# IoTSchem.net
KiCad netlist of a schematic drawn in EAGLE
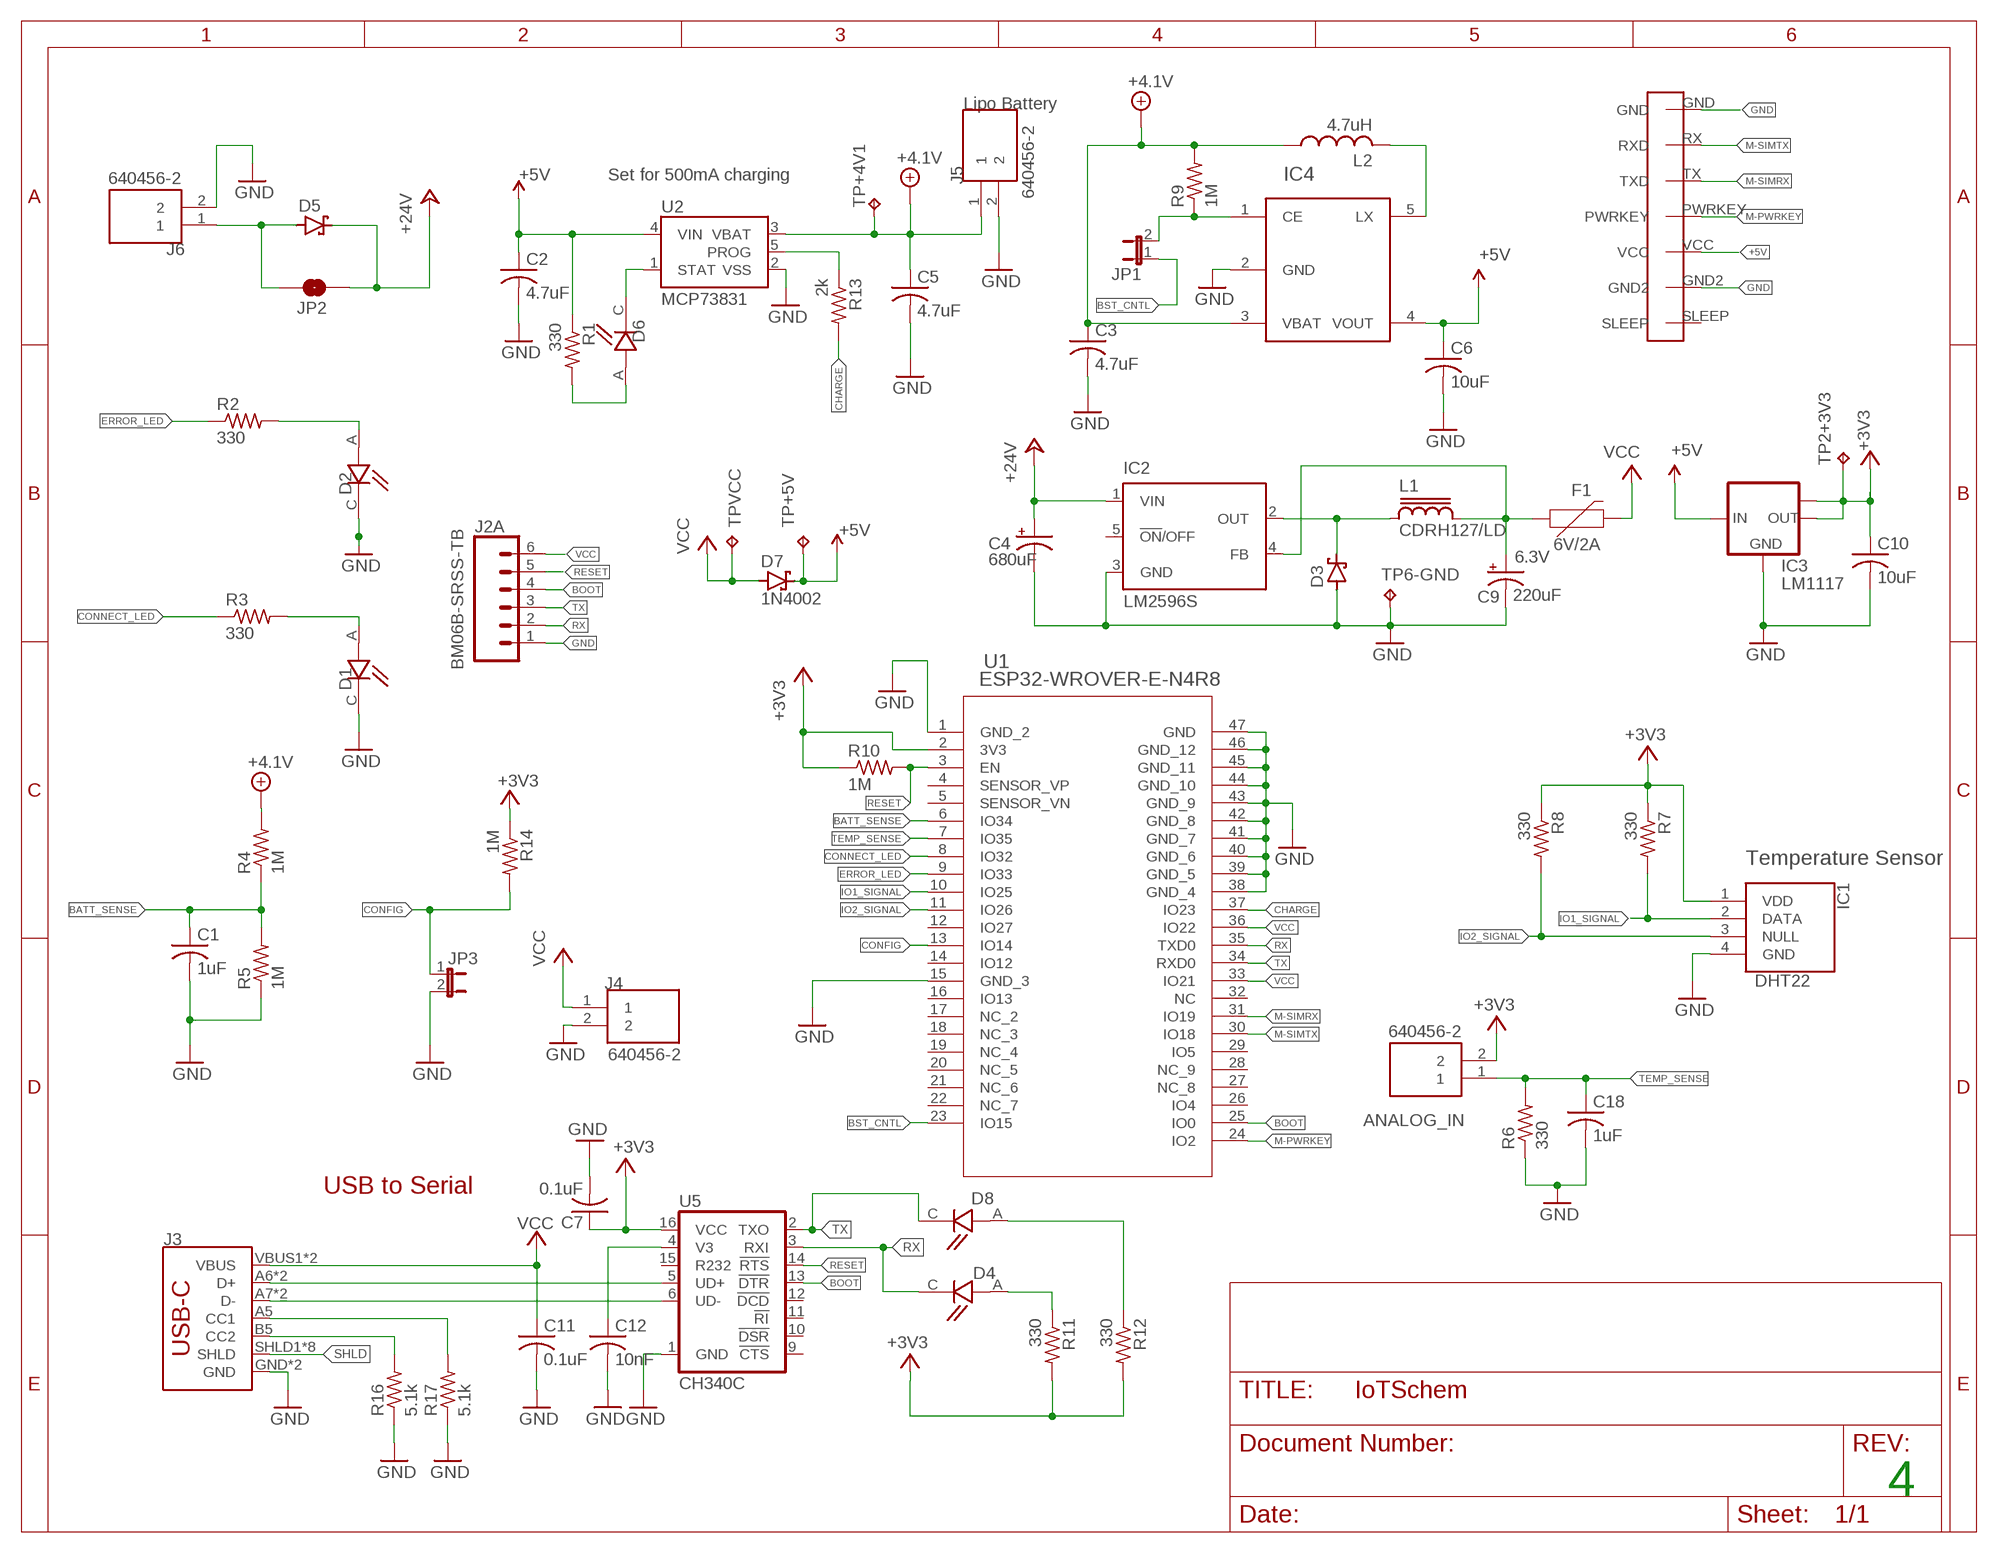
[diagram p0: schematic, sheet 1]

(export (version "E")
  (design (tool "Eeschema 10.0.6"))
  (components
    (comp (ref "ANALOG_IN")
      (value "640456-2")
      (footprint "eagle-import:TE_640456-2")
      (fields (field (name "DIGI-KEY_PART_NUMBER") "A1921-ND") (field (name "MF") "TE Connectivity"))
      (libsource (lib "eagle-import") (part "640456-2"))
    )
    (comp (ref "C1")
      (value "1uF")
      (footprint "eagle-import:C0805")
      (fields (field (name "DIGIKEYPART#") "311-1365-1-ND"))
      (libsource (lib "eagle-import") (part "C-USC0805"))
    )
    (comp (ref "C2")
      (value "4.7uF")
      (footprint "eagle-import:C0805")
      (fields (field (name "DIGIKEYPART#") "1276-6722-1-ND"))
      (libsource (lib "eagle-import") (part "C-USC0805"))
    )
    (comp (ref "C3")
      (value "4.7uF")
      (footprint "eagle-import:C0805")
      (fields (field (name "DIGIKEYPART#") "1276-6722-1-ND"))
      (libsource (lib "eagle-import") (part "C-USC0805"))
    )
    (comp (ref "C4")
      (value "680uF")
      (footprint "eagle-import:E5-10,5")
      (fields (field (name "VOLTAGE") "25V"))
      (libsource (lib "eagle-import") (part "CPOL-USE5-10.5"))
    )
    (comp (ref "C5")
      (value "4.7uF")
      (footprint "eagle-import:C0805")
      (fields (field (name "DIGIKEYPART#") "1276-6722-1-ND"))
      (libsource (lib "eagle-import") (part "C-USC0805"))
    )
    (comp (ref "C6")
      (value "10uF")
      (footprint "eagle-import:C0805")
      (libsource (lib "eagle-import") (part "C-USC0805"))
    )
    (comp (ref "C7")
      (value "0.1uF")
      (footprint "eagle-import:C0805")
      (fields (field (name "DIGIKEYPART#") "311-1140-1-ND"))
      (libsource (lib "eagle-import") (part "C-USC0805"))
    )
    (comp (ref "C9")
      (value "220uF")
      (footprint "eagle-import:UD-6,3X5,8_NICHICON")
      (fields (field (name "VOLTAGE") "6.3V"))
      (libsource (lib "eagle-import") (part "CPOL-USUD-6,3X5,8"))
    )
    (comp (ref "C10")
      (value "10uF")
      (footprint "eagle-import:C0805")
      (fields (field (name "DIGIKEYPART#") "399-C0805C106K8PAC7800CT-ND"))
      (libsource (lib "eagle-import") (part "C-USC0805"))
    )
    (comp (ref "C11")
      (value "0.1uF")
      (footprint "eagle-import:C0805")
      (fields (field (name "DIGIKEYPART#") "311-1140-1-ND"))
      (libsource (lib "eagle-import") (part "C-USC0805"))
    )
    (comp (ref "C12")
      (value "10nF")
      (footprint "eagle-import:C0805")
      (fields (field (name "DIGIKEYPART#") "1276-1015-1-ND"))
      (libsource (lib "eagle-import") (part "C-USC0805"))
    )
    (comp (ref "C18")
      (value "1uF")
      (footprint "eagle-import:C0805")
      (fields (field (name "DIGIKEYPART#") "311-1365-1-ND"))
      (libsource (lib "eagle-import") (part "C-USC0805"))
    )
    (comp (ref "D1")
      (value "5988170107F")
      (footprint "eagle-import:LEDC2012X70N")
      (fields (field (name "DIGI-KEY_PART_NUMBER") "350-2044-1-ND") (field (name "MF") "Dialight"))
      (libsource (lib "eagle-import") (part "5988170107F"))
    )
    (comp (ref "D2")
      (value "5988170107F")
      (footprint "eagle-import:LEDC2012X70N")
      (fields (field (name "DIGI-KEY_PART_NUMBER") "350-2044-1-ND") (field (name "MF") "Dialight"))
      (libsource (lib "eagle-import") (part "5988170107F"))
    )
    (comp (ref "D3")
      (value "SCHOTTKY-DIODESMD")
      (footprint "eagle-import:SMB")
      (libsource (lib "eagle-import") (part "SCHOTTKY-DIODESMD"))
    )
    (comp (ref "D4")
      (value "5988170107F")
      (footprint "eagle-import:LEDC2012X70N")
      (fields (field (name "DIGI-KEY_PART_NUMBER") "350-2044-1-ND") (field (name "MF") "Dialight"))
      (libsource (lib "eagle-import") (part "5988170107F"))
    )
    (comp (ref "D5")
      (value "1N4002")
      (footprint "eagle-import:SMB")
      (libsource (lib "eagle-import") (part "SCHOTTKY-DIODESMD"))
    )
    (comp (ref "D6")
      (value "5988170107F")
      (footprint "eagle-import:LEDC2012X70N")
      (fields (field (name "DIGI-KEY_PART_NUMBER") "350-2044-1-ND") (field (name "MF") "Dialight"))
      (libsource (lib "eagle-import") (part "5988170107F"))
    )
    (comp (ref "D7")
      (value "1N4002")
      (footprint "eagle-import:SMB")
      (libsource (lib "eagle-import") (part "SCHOTTKY-DIODESMD"))
    )
    (comp (ref "D8")
      (value "5988170107F")
      (footprint "eagle-import:LEDC2012X70N")
      (fields (field (name "DIGI-KEY_PART_NUMBER") "350-2044-1-ND") (field (name "MF") "Dialight"))
      (libsource (lib "eagle-import") (part "5988170107F"))
    )
    (comp (ref "F1")
      (value "6V/2A")
      (footprint "eagle-import:1210")
      (libsource (lib "eagle-import") (part "PPTC_6V2A"))
    )
    (comp (ref "IC1")
      (value "DHT22")
      (footprint "eagle-import:DHT22")
      (fields (field (name "DIGIKEYPART#") "1528-1504-ND"))
      (libsource (lib "eagle-import") (part "DHT22"))
    )
    (comp (ref "IC2")
      (value "LM2596S")
      (footprint "eagle-import:TO263-5")
      (fields
        (field (name "MF") "NATIONAL SEMICONDUCTOR")
        (field (name "MPN") "LM2596S-ADJ/NOPB")
        (field (name "DIGIKEYPART#") "2156-LM2596SX-5.0/NOPB-ND")
      )
      (libsource (lib "eagle-import") (part "LM2596S"))
    )
    (comp (ref "IC3")
      (value "LM1117MPX-3.3")
      (footprint "eagle-import:SOT223")
      (fields (field (name "DIGIKEYPART#") "LM1117IMP-3.3/NOPBCT-ND"))
      (libsource (lib "eagle-import") (part "LM1117MPX-3.3"))
    )
    (comp (ref "IC4")
      (value "XC9140")
      (footprint "eagle-import:SOT-25")
      (fields (field (name "DIGIKEYPART#") "893-1181-1-ND"))
      (libsource (lib "eagle-import") (part "XC9140"))
    )
    (comp (ref "J1")
      (value "SIM7000A")
      (footprint "eagle-import:SIM7000A")
      (libsource (lib "eagle-import") (part "SIM7000A"))
    )
    (comp (ref "J2")
      (value "BM06B-SRSS-TB")
      (footprint "eagle-import:JST-6-SMD-HORI-1.0MM")
      (libsource (lib "eagle-import") (part "JST_6_PIN_HORIZONTAL"))
    )
    (comp (ref "J3")
      (value "USB_C16PIN")
      (footprint "eagle-import:USB-C-16P")
      (libsource (lib "eagle-import") (part "USB_C16PIN"))
    )
    (comp (ref "J4")
      (value "640456-2")
      (footprint "eagle-import:TE_640456-2")
      (fields (field (name "DIGI-KEY_PART_NUMBER") "A1921-ND") (field (name "MF") "TE Connectivity"))
      (libsource (lib "eagle-import") (part "640456-2"))
    )
    (comp (ref "J5")
      (value "640456-2")
      (footprint "eagle-import:TE_640456-2")
      (fields (field (name "DIGI-KEY_PART_NUMBER") "A1921-ND") (field (name "MF") "TE Connectivity"))
      (libsource (lib "eagle-import") (part "640456-2"))
    )
    (comp (ref "J6")
      (value "640456-2")
      (footprint "eagle-import:TE_640456-2")
      (fields (field (name "DIGI-KEY_PART_NUMBER") "A1921-ND") (field (name "MF") "TE Connectivity"))
      (libsource (lib "eagle-import") (part "640456-2"))
    )
    (comp (ref "JP1")
      (value "JP1E")
      (footprint "eagle-import:JP1")
      (libsource (lib "eagle-import") (part "JP1E"))
    )
    (comp (ref "JP2")
      (value "JUMPER-SMT_2_NO_SILK")
      (footprint "eagle-import:SMT-JUMPER_2_NO_SILK")
      (libsource (lib "eagle-import") (part "JUMPER-SMT_2_NO_SILK"))
    )
    (comp (ref "JP3")
      (value "JP1E")
      (footprint "eagle-import:JP1")
      (libsource (lib "eagle-import") (part "JP1E"))
    )
    (comp (ref "L1")
      (value "CDRH127/LD")
      (footprint "eagle-import:CDRH127_LD")
      (libsource (lib "eagle-import") (part "CDRH127/LD"))
    )
    (comp (ref "L2")
      (value "4.7uH")
      (footprint "eagle-import:L2825P")
      (libsource (lib "eagle-import") (part "L-USL2825P"))
    )
    (comp (ref "R1")
      (value "330")
      (footprint "eagle-import:R0805")
      (libsource (lib "eagle-import") (part "R-US_R0805"))
    )
    (comp (ref "R2")
      (value "330")
      (footprint "eagle-import:R0805")
      (fields (field (name "DIGIKEYPART#") "RMCF0805JT330RCT-ND"))
      (libsource (lib "eagle-import") (part "R-US_R0805"))
    )
    (comp (ref "R3")
      (value "330")
      (footprint "eagle-import:R0805")
      (fields (field (name "DIGIKEYPART#") "RMCF0805JT330RCT-ND"))
      (libsource (lib "eagle-import") (part "R-US_R0805"))
    )
    (comp (ref "R4")
      (value "1M")
      (footprint "eagle-import:R0805")
      (fields (field (name "DIGIKEYPART#") "RMCF0805JT1M00CT-ND"))
      (libsource (lib "eagle-import") (part "R-US_R0805"))
    )
    (comp (ref "R5")
      (value "1M")
      (footprint "eagle-import:R0805")
      (fields (field (name "DIGIKEYPART#") "RMCF0805JT1M00CT-ND"))
      (libsource (lib "eagle-import") (part "R-US_R0805"))
    )
    (comp (ref "R6")
      (value "330")
      (footprint "eagle-import:R0805")
      (fields (field (name "DIGIKEYPART#") "RMCF0805JT330RCT-ND"))
      (libsource (lib "eagle-import") (part "R-US_R0805"))
    )
    (comp (ref "R7")
      (value "330")
      (footprint "eagle-import:R0805")
      (fields (field (name "DIGIKEYPART#") "RMCF0805JT330RCT-ND"))
      (libsource (lib "eagle-import") (part "R-US_R0805"))
    )
    (comp (ref "R8")
      (value "330")
      (footprint "eagle-import:R0805")
      (fields (field (name "DIGIKEYPART#") "RMCF0805JT330RCT-ND"))
      (libsource (lib "eagle-import") (part "R-US_R0805"))
    )
    (comp (ref "R9")
      (value "1M")
      (footprint "eagle-import:R0805")
      (fields (field (name "DIGIKEYPART#") "RMCF0805JT1M00CT-ND"))
      (libsource (lib "eagle-import") (part "R-US_R0805"))
    )
    (comp (ref "R10")
      (value "1M")
      (footprint "eagle-import:R0805")
      (fields (field (name "DIGIKEYPART#") "RMCF0805JT1M00CT-ND"))
      (libsource (lib "eagle-import") (part "R-US_R0805"))
    )
    (comp (ref "R11")
      (value "330")
      (footprint "eagle-import:R0805")
      (fields (field (name "DIGIKEYPART#") "RMCF0805JT330RCT-ND"))
      (libsource (lib "eagle-import") (part "R-US_R0805"))
    )
    (comp (ref "R12")
      (value "330")
      (footprint "eagle-import:R0805")
      (fields (field (name "DIGIKEYPART#") "RMCF0805JT330RCT-ND"))
      (libsource (lib "eagle-import") (part "R-US_R0805"))
    )
    (comp (ref "R13")
      (value "2k")
      (footprint "eagle-import:R0805")
      (fields (field (name "DIGIKEYPART#") "RMCF0805FT2K00CT-ND"))
      (libsource (lib "eagle-import") (part "R-US_R0805"))
    )
    (comp (ref "R14")
      (value "1M")
      (footprint "eagle-import:R0805")
      (fields (field (name "DIGIKEYPART#") "RMCF0805JT1M00CT-ND"))
      (libsource (lib "eagle-import") (part "R-US_R0805"))
    )
    (comp (ref "R16")
      (value "5.1k")
      (footprint "eagle-import:R0805")
      (fields (field (name "DIGIKEYPART#") "RMCF0805JT5K10CT-ND"))
      (libsource (lib "eagle-import") (part "R-US_R0805"))
    )
    (comp (ref "R17")
      (value "5.1k")
      (footprint "eagle-import:R0805")
      (fields (field (name "DIGIKEYPART#") "RMCF0805JT5K10CT-ND"))
      (libsource (lib "eagle-import") (part "R-US_R0805"))
    )
    (comp (ref "TP+4V1")
      (value "TPB1,27")
      (footprint "eagle-import:B1,27")
      (libsource (lib "eagle-import") (part "TPB1,27"))
    )
    (comp (ref "TP+5V")
      (value "TPB1,27")
      (footprint "eagle-import:B1,27")
      (libsource (lib "eagle-import") (part "TPB1,27"))
    )
    (comp (ref "TP2+3V3")
      (value "TPB1,27")
      (footprint "eagle-import:B1,27")
      (libsource (lib "eagle-import") (part "TPB1,27"))
    )
    (comp (ref "TP6-GND")
      (value "TPB1,27")
      (footprint "eagle-import:B1,27")
      (libsource (lib "eagle-import") (part "TPB1,27"))
    )
    (comp (ref "TPVCC")
      (value "TPB1,27")
      (footprint "eagle-import:B1,27")
      (libsource (lib "eagle-import") (part "TPB1,27"))
    )
    (comp (ref "U1")
      (value "ESP32-WROVER-E-N4R8")
      (footprint "eagle-import:ESP32­WROVER­E_ESP32­WROVER­IE")
      (fields (field (name "COPYRIGHT") "Copyright (C) 2022 Ultra Librarian. All rights reserved."))
      (libsource (lib "eagle-import") (part "ESP32-WROVER-E-N4R8"))
    )
    (comp (ref "U2")
      (value "MCP73831")
      (footprint "eagle-import:SOT23-5")
      (fields (field (name "DIGIKEYPART#") "MCP73831T-2DCI/OTCT-ND"))
      (libsource (lib "eagle-import") (part "MCP73831"))
    )
    (comp (ref "U5")
      (value "CH340C")
      (footprint "eagle-import:SO016")
      (libsource (lib "eagle-import") (part "CH340C"))
    )
  )
  (nets
    (net (code "1") (name "+3V3") (class "Default")
      (node (ref "ANALOG_IN") (pin "2") (pinfunction "2_2") (pintype "passive"))
      (node (ref "C10") (pin "1") (pinfunction "1_1") (pintype "passive"))
      (node (ref "C7") (pin "1") (pinfunction "1_1") (pintype "passive"))
      (node (ref "IC1") (pin "1") (pinfunction "VDD_1") (pintype "bidirectional"))
      (node (ref "IC3") (pin "2") (pinfunction "OUT_2") (pintype "passive"))
      (node (ref "IC3") (pin "TAB") (pinfunction "OUT1_TAB") (pintype "passive"))
      (node (ref "R10") (pin "1") (pinfunction "1_1") (pintype "passive"))
      (node (ref "R11") (pin "2") (pinfunction "2_2") (pintype "passive"))
      (node (ref "R12") (pin "2") (pinfunction "2_2") (pintype "passive"))
      (node (ref "R14") (pin "1") (pinfunction "1_1") (pintype "passive"))
      (node (ref "R7") (pin "1") (pinfunction "1_1") (pintype "passive"))
      (node (ref "R8") (pin "1") (pinfunction "1_1") (pintype "passive"))
      (node (ref "TP2+3V3") (pin "TP") (pinfunction "TP_TP") (pintype "input"))
      (node (ref "U1") (pin "2") (pinfunction "3V3_2") (pintype "power_in"))
      (node (ref "U5") (pin "16") (pinfunction "VCC_16") (pintype "bidirectional"))
    )
    (net (code "2") (name "+4.1V") (class "Default")
      (node (ref "C3") (pin "1") (pinfunction "1_1") (pintype "passive"))
      (node (ref "C5") (pin "1") (pinfunction "1_1") (pintype "passive"))
      (node (ref "IC4") (pin "3") (pinfunction "VBAT_3") (pintype "bidirectional"))
      (node (ref "J5") (pin "1") (pinfunction "1_1") (pintype "passive"))
      (node (ref "L2") (pin "1") (pinfunction "1_1") (pintype "passive"))
      (node (ref "R4") (pin "2") (pinfunction "2_2") (pintype "passive"))
      (node (ref "R9") (pin "2") (pinfunction "2_2") (pintype "passive"))
      (node (ref "TP+4V1") (pin "TP") (pinfunction "TP_TP") (pintype "input"))
      (node (ref "U2") (pin "3") (pinfunction "VBAT_3") (pintype "power_in"))
    )
    (net (code "3") (name "+5V") (class "Default")
      (node (ref "C2") (pin "1") (pinfunction "1_1") (pintype "passive"))
      (node (ref "C6") (pin "1") (pinfunction "1_1") (pintype "passive"))
      (node (ref "D7") (pin "C") (pinfunction "C_C") (pintype "passive"))
      (node (ref "IC3") (pin "3") (pinfunction "IN_3") (pintype "input"))
      (node (ref "IC4") (pin "4") (pinfunction "VOUT_4") (pintype "bidirectional"))
      (node (ref "J1") (pin "VCC") (pinfunction "VCC_VCC") (pintype "bidirectional"))
      (node (ref "R1") (pin "1") (pinfunction "1_1") (pintype "passive"))
      (node (ref "TP+5V") (pin "TP") (pinfunction "TP_TP") (pintype "input"))
      (node (ref "U2") (pin "4") (pinfunction "VIN_4") (pintype "power_in"))
    )
    (net (code "4") (name "+24V") (class "Default")
      (node (ref "C4") (pin "+") (pinfunction "+_+") (pintype "passive"))
      (node (ref "D5") (pin "C") (pinfunction "C_C") (pintype "passive"))
      (node (ref "IC2") (pin "1") (pinfunction "VIN_1") (pintype "input"))
      (node (ref "JP2") (pin "2") (pinfunction "2_2") (pintype "passive"))
    )
    (net (code "5") (name "BATT_SENSE") (class "Default")
      (node (ref "C1") (pin "1") (pinfunction "1_1") (pintype "passive"))
      (node (ref "R4") (pin "1") (pinfunction "1_1") (pintype "passive"))
      (node (ref "R5") (pin "2") (pinfunction "2_2") (pintype "passive"))
      (node (ref "U1") (pin "6") (pinfunction "IO34_6") (pintype "input"))
    )
    (net (code "6") (name "BOOT") (class "Default")
      (node (ref "J2") (pin "4") (pinfunction "4_4") (pintype "passive"))
      (node (ref "U1") (pin "25") (pinfunction "IO0_25") (pintype "bidirectional"))
      (node (ref "U5") (pin "13") (pinfunction "~{DTR}_13") (pintype "bidirectional"))
    )
    (net (code "7") (name "BST_CNTL") (class "Default")
      (node (ref "JP1") (pin "1") (pinfunction "1_1") (pintype "passive"))
      (node (ref "U1") (pin "23") (pinfunction "IO15_23") (pintype "bidirectional"))
    )
    (net (code "8") (name "CHARGE") (class "Default")
      (node (ref "R13") (pin "1") (pinfunction "1_1") (pintype "passive"))
      (node (ref "U1") (pin "37") (pinfunction "IO23_37") (pintype "bidirectional"))
      (node (ref "U2") (pin "5") (pinfunction "PROG_5") (pintype "input"))
    )
    (net (code "9") (name "CONFIG") (class "Default")
      (node (ref "JP3") (pin "1") (pinfunction "1_1") (pintype "passive"))
      (node (ref "R14") (pin "2") (pinfunction "2_2") (pintype "passive"))
      (node (ref "U1") (pin "13") (pinfunction "IO14_13") (pintype "bidirectional"))
    )
    (net (code "10") (name "CONNECT_LED") (class "Default")
      (node (ref "R3") (pin "1") (pinfunction "1_1") (pintype "passive"))
      (node (ref "U1") (pin "8") (pinfunction "IO32_8") (pintype "bidirectional"))
    )
    (net (code "11") (name "ERROR_LED") (class "Default")
      (node (ref "R2") (pin "1") (pinfunction "1_1") (pintype "passive"))
      (node (ref "U1") (pin "9") (pinfunction "IO33_9") (pintype "bidirectional"))
    )
    (net (code "12") (name "GND") (class "Default")
      (node (ref "C1") (pin "2") (pinfunction "2_2") (pintype "passive"))
      (node (ref "C10") (pin "2") (pinfunction "2_2") (pintype "passive"))
      (node (ref "C11") (pin "2") (pinfunction "2_2") (pintype "passive"))
      (node (ref "C12") (pin "2") (pinfunction "2_2") (pintype "passive"))
      (node (ref "C18") (pin "2") (pinfunction "2_2") (pintype "passive"))
      (node (ref "C2") (pin "2") (pinfunction "2_2") (pintype "passive"))
      (node (ref "C3") (pin "2") (pinfunction "2_2") (pintype "passive"))
      (node (ref "C4") (pin "-") (pinfunction "-_-") (pintype "passive"))
      (node (ref "C5") (pin "2") (pinfunction "2_2") (pintype "passive"))
      (node (ref "C6") (pin "2") (pinfunction "2_2") (pintype "passive"))
      (node (ref "C7") (pin "2") (pinfunction "2_2") (pintype "passive"))
      (node (ref "C9") (pin "-") (pinfunction "-_-") (pintype "passive"))
      (node (ref "D1") (pin "C") (pinfunction "C_C") (pintype "passive"))
      (node (ref "D2") (pin "C") (pinfunction "C_C") (pintype "passive"))
      (node (ref "D3") (pin "A") (pinfunction "A_A") (pintype "passive"))
      (node (ref "IC1") (pin "4") (pinfunction "GND_4") (pintype "bidirectional"))
      (node (ref "IC2") (pin "3") (pinfunction "GND_3") (pintype "power_in"))
      (node (ref "IC3") (pin "1") (pinfunction "GND_1") (pintype "input"))
      (node (ref "IC4") (pin "2") (pinfunction "GND_2") (pintype "bidirectional"))
      (node (ref "J1") (pin "GND") (pinfunction "GND_GND") (pintype "bidirectional"))
      (node (ref "J1") (pin "GND2") (pinfunction "GND2_GND2") (pintype "bidirectional"))
      (node (ref "J2") (pin "1") (pinfunction "1_1") (pintype "passive"))
      (node (ref "J3") (pin "GND") (pinfunction "GND_GND") (pintype "bidirectional"))
      (node (ref "J3") (pin "GND2") (pinfunction "GND_GND2") (pintype "bidirectional"))
      (node (ref "J4") (pin "2") (pinfunction "2_2") (pintype "passive"))
      (node (ref "J5") (pin "2") (pinfunction "2_2") (pintype "passive"))
      (node (ref "J6") (pin "2") (pinfunction "2_2") (pintype "passive"))
      (node (ref "JP3") (pin "2") (pinfunction "2_2") (pintype "passive"))
      (node (ref "R16") (pin "1") (pinfunction "1_1") (pintype "passive"))
      (node (ref "R17") (pin "1") (pinfunction "1_1") (pintype "passive"))
      (node (ref "R5") (pin "1") (pinfunction "1_1") (pintype "passive"))
      (node (ref "R6") (pin "1") (pinfunction "1_1") (pintype "passive"))
      (node (ref "TP6-GND") (pin "TP") (pinfunction "TP_TP") (pintype "input"))
      (node (ref "U1") (pin "1") (pinfunction "GND_2_1") (pintype "passive"))
      (node (ref "U1") (pin "15") (pinfunction "GND_3_15") (pintype "passive"))
      (node (ref "U1") (pin "38") (pinfunction "GND_4_38") (pintype "passive"))
      (node (ref "U1") (pin "39") (pinfunction "GND_5_39") (pintype "passive"))
      (node (ref "U1") (pin "40") (pinfunction "GND_6_40") (pintype "passive"))
      (node (ref "U1") (pin "41") (pinfunction "GND_7_41") (pintype "passive"))
      (node (ref "U1") (pin "42") (pinfunction "GND_8_42") (pintype "passive"))
      (node (ref "U1") (pin "43") (pinfunction "GND_9_43") (pintype "passive"))
      (node (ref "U1") (pin "44") (pinfunction "GND_10_44") (pintype "passive"))
      (node (ref "U1") (pin "45") (pinfunction "GND_11_45") (pintype "passive"))
      (node (ref "U1") (pin "46") (pinfunction "GND_12_46") (pintype "passive"))
      (node (ref "U1") (pin "47") (pinfunction "GND_47") (pintype "passive"))
      (node (ref "U2") (pin "2") (pinfunction "VSS_2") (pintype "power_in"))
      (node (ref "U5") (pin "1") (pinfunction "GND_1") (pintype "bidirectional"))
    )
    (net (code "13") (name "IO1_SIGNAL") (class "Default")
      (node (ref "IC1") (pin "2") (pinfunction "DATA_2") (pintype "bidirectional"))
      (node (ref "R7") (pin "2") (pinfunction "2_2") (pintype "passive"))
      (node (ref "U1") (pin "10") (pinfunction "IO25_10") (pintype "bidirectional"))
    )
    (net (code "14") (name "IO2_SIGNAL") (class "Default")
      (node (ref "IC1") (pin "3") (pinfunction "NULL_3") (pintype "bidirectional"))
      (node (ref "R8") (pin "2") (pinfunction "2_2") (pintype "passive"))
      (node (ref "U1") (pin "11") (pinfunction "IO26_11") (pintype "bidirectional"))
    )
    (net (code "15") (name "M-PWRKEY") (class "Default")
      (node (ref "J1") (pin "PWRKEY") (pinfunction "PWRKEY_PWRKEY") (pintype "bidirectional"))
      (node (ref "U1") (pin "24") (pinfunction "IO2_24") (pintype "bidirectional"))
    )
    (net (code "16") (name "M-SIMRX") (class "Default")
      (node (ref "J1") (pin "TX") (pinfunction "TXD_TX") (pintype "bidirectional"))
      (node (ref "U1") (pin "31") (pinfunction "IO19_31") (pintype "bidirectional"))
    )
    (net (code "17") (name "M-SIMTX") (class "Default")
      (node (ref "J1") (pin "RX") (pinfunction "RXD_RX") (pintype "bidirectional"))
      (node (ref "U1") (pin "30") (pinfunction "IO18_30") (pintype "bidirectional"))
    )
    (net (code "18") (name "Net-(D1-PadA)") (class "Default")
      (node (ref "D1") (pin "A") (pinfunction "A_A") (pintype "passive"))
      (node (ref "R3") (pin "2") (pinfunction "2_2") (pintype "passive"))
    )
    (net (code "19") (name "Net-(D2-PadA)") (class "Default")
      (node (ref "D2") (pin "A") (pinfunction "A_A") (pintype "passive"))
      (node (ref "R2") (pin "2") (pinfunction "2_2") (pintype "passive"))
    )
    (net (code "20") (name "Net-(D4-PadA)") (class "Default")
      (node (ref "D4") (pin "A") (pinfunction "A_A") (pintype "passive"))
      (node (ref "R11") (pin "1") (pinfunction "1_1") (pintype "passive"))
    )
    (net (code "21") (name "Net-(D5-PadA)") (class "Default")
      (node (ref "D5") (pin "A") (pinfunction "A_A") (pintype "passive"))
      (node (ref "J6") (pin "1") (pinfunction "1_1") (pintype "passive"))
      (node (ref "JP2") (pin "1") (pinfunction "1_1") (pintype "passive"))
    )
    (net (code "22") (name "Net-(D6-PadA)") (class "Default")
      (node (ref "D6") (pin "A") (pinfunction "A_A") (pintype "passive"))
      (node (ref "R1") (pin "2") (pinfunction "2_2") (pintype "passive"))
    )
    (net (code "23") (name "Net-(D8-PadA)") (class "Default")
      (node (ref "D8") (pin "A") (pinfunction "A_A") (pintype "passive"))
      (node (ref "R12") (pin "1") (pinfunction "1_1") (pintype "passive"))
    )
    (net (code "24") (name "Net-(IC2-FB)") (class "Default")
      (node (ref "C9") (pin "+") (pinfunction "+_+") (pintype "passive"))
      (node (ref "F1") (pin "1") (pinfunction "1_1") (pintype "bidirectional"))
      (node (ref "IC2") (pin "4") (pinfunction "FB_4") (pintype "input"))
      (node (ref "L1") (pin "2") (pinfunction "2_2") (pintype "passive"))
    )
    (net (code "25") (name "Net-(IC2-OUT)") (class "Default")
      (node (ref "D3") (pin "C") (pinfunction "C_C") (pintype "passive"))
      (node (ref "IC2") (pin "2") (pinfunction "OUT_2") (pintype "output"))
      (node (ref "L1") (pin "1") (pinfunction "1_1") (pintype "passive"))
    )
    (net (code "26") (name "Net-(IC4-CE)") (class "Default")
      (node (ref "IC4") (pin "1") (pinfunction "CE_1") (pintype "bidirectional"))
      (node (ref "JP1") (pin "2") (pinfunction "2_2") (pintype "passive"))
      (node (ref "R9") (pin "1") (pinfunction "1_1") (pintype "passive"))
    )
    (net (code "27") (name "Net-(IC4-LX)") (class "Default")
      (node (ref "IC4") (pin "5") (pinfunction "LX_5") (pintype "bidirectional"))
      (node (ref "L2") (pin "2") (pinfunction "2_2") (pintype "passive"))
    )
    (net (code "28") (name "Net-(J3-CC1)") (class "Default")
      (node (ref "J3") (pin "A5") (pinfunction "CC1_A5") (pintype "bidirectional"))
      (node (ref "R17") (pin "2") (pinfunction "2_2") (pintype "passive"))
    )
    (net (code "29") (name "Net-(J3-CC2)") (class "Default")
      (node (ref "J3") (pin "B5") (pinfunction "CC2_B5") (pintype "bidirectional"))
      (node (ref "R16") (pin "2") (pinfunction "2_2") (pintype "passive"))
    )
    (net (code "30") (name "Net-(U2-STAT)") (class "Default")
      (node (ref "D6") (pin "C") (pinfunction "C_C") (pintype "passive"))
      (node (ref "U2") (pin "1") (pinfunction "STAT_1") (pintype "output"))
    )
    (net (code "31") (name "Net-(U5-UD+)") (class "Default")
      (node (ref "J3") (pin "A6") (pinfunction "D+_A6") (pintype "bidirectional"))
      (node (ref "J3") (pin "B6") (pinfunction "D+_B6") (pintype "bidirectional"))
      (node (ref "U5") (pin "5") (pinfunction "UD+_5") (pintype "bidirectional"))
    )
    (net (code "32") (name "Net-(U5-UD-)") (class "Default")
      (node (ref "J3") (pin "A7") (pinfunction "D-_A7") (pintype "bidirectional"))
      (node (ref "J3") (pin "B7") (pinfunction "D-_B7") (pintype "bidirectional"))
      (node (ref "U5") (pin "6") (pinfunction "UD-_6") (pintype "bidirectional"))
    )
    (net (code "33") (name "Net-(U5-V3)") (class "Default")
      (node (ref "C12") (pin "1") (pinfunction "1_1") (pintype "passive"))
      (node (ref "U5") (pin "4") (pinfunction "V3_4") (pintype "bidirectional"))
    )
    (net (code "34") (name "RESET") (class "Default")
      (node (ref "J2") (pin "5") (pinfunction "5_5") (pintype "passive"))
      (node (ref "R10") (pin "2") (pinfunction "2_2") (pintype "passive"))
      (node (ref "U1") (pin "3") (pinfunction "EN_3") (pintype "input"))
      (node (ref "U5") (pin "14") (pinfunction "~{RTS}_14") (pintype "bidirectional"))
    )
    (net (code "35") (name "RX") (class "Default")
      (node (ref "D4") (pin "C") (pinfunction "C_C") (pintype "passive"))
      (node (ref "J2") (pin "2") (pinfunction "2_2") (pintype "passive"))
      (node (ref "U1") (pin "35") (pinfunction "TXD0_35") (pintype "bidirectional"))
      (node (ref "U5") (pin "3") (pinfunction "RXI_3") (pintype "bidirectional"))
    )
    (net (code "36") (name "SHLD") (class "Default")
      (node (ref "J3") (pin "SHLD1") (pinfunction "SHLD_SHLD1") (pintype "bidirectional"))
      (node (ref "J3") (pin "SHLD2") (pinfunction "SHLD_SHLD2") (pintype "bidirectional"))
      (node (ref "J3") (pin "SHLD3") (pinfunction "SHLD_SHLD3") (pintype "bidirectional"))
      (node (ref "J3") (pin "SHLD4") (pinfunction "SHLD_SHLD4") (pintype "bidirectional"))
      (node (ref "J3") (pin "SHLD5") (pinfunction "SHLD_SHLD5") (pintype "bidirectional"))
      (node (ref "J3") (pin "SHLD6") (pinfunction "SHLD_SHLD6") (pintype "bidirectional"))
      (node (ref "J3") (pin "SHLD7") (pinfunction "SHLD_SHLD7") (pintype "bidirectional"))
      (node (ref "J3") (pin "SHLD8") (pinfunction "SHLD_SHLD8") (pintype "bidirectional"))
    )
    (net (code "37") (name "TEMP_SENSE") (class "Default")
      (node (ref "ANALOG_IN") (pin "1") (pinfunction "1_1") (pintype "passive"))
      (node (ref "C18") (pin "1") (pinfunction "1_1") (pintype "passive"))
      (node (ref "R6") (pin "2") (pinfunction "2_2") (pintype "passive"))
      (node (ref "U1") (pin "7") (pinfunction "IO35_7") (pintype "input"))
    )
    (net (code "38") (name "TX") (class "Default")
      (node (ref "D8") (pin "C") (pinfunction "C_C") (pintype "passive"))
      (node (ref "J2") (pin "3") (pinfunction "3_3") (pintype "passive"))
      (node (ref "U1") (pin "34") (pinfunction "RXD0_34") (pintype "bidirectional"))
      (node (ref "U5") (pin "2") (pinfunction "TXO_2") (pintype "bidirectional"))
    )
    (net (code "39") (name "VCC") (class "Default")
      (node (ref "C11") (pin "1") (pinfunction "1_1") (pintype "passive"))
      (node (ref "D7") (pin "A") (pinfunction "A_A") (pintype "passive"))
      (node (ref "F1") (pin "2") (pinfunction "2_2") (pintype "bidirectional"))
      (node (ref "J2") (pin "6") (pinfunction "6_6") (pintype "passive"))
      (node (ref "J3") (pin "VBUS1") (pinfunction "VBUS_VBUS1") (pintype "bidirectional"))
      (node (ref "J3") (pin "VBUS2") (pinfunction "VBUS_VBUS2") (pintype "bidirectional"))
      (node (ref "J4") (pin "1") (pinfunction "1_1") (pintype "passive"))
      (node (ref "TPVCC") (pin "TP") (pinfunction "TP_TP") (pintype "input"))
      (node (ref "U1") (pin "33") (pinfunction "IO21_33") (pintype "bidirectional"))
      (node (ref "U1") (pin "36") (pinfunction "IO22_36") (pintype "bidirectional"))
    )
    (net (code "40") (name "unconnected-(IC2-~{ON}{slash}OFF-Pad5)") (class "Default")
      (node (ref "IC2") (pin "5") (pinfunction "~{ON}/OFF_5") (pintype "input"))
    )
    (net (code "41") (name "unconnected-(J1-PadSLEEP)") (class "Default")
      (node (ref "J1") (pin "SLEEP") (pinfunction "SLEEP_SLEEP") (pintype "bidirectional"))
    )
    (net (code "42") (name "unconnected-(R13-Pad2)") (class "Default")
      (node (ref "R13") (pin "2") (pinfunction "2_2") (pintype "passive"))
    )
    (net (code "43") (name "unconnected-(U1-IO4-Pad26)") (class "Default")
      (node (ref "U1") (pin "26") (pinfunction "IO4_26") (pintype "bidirectional"))
    )
    (net (code "44") (name "unconnected-(U1-IO5-Pad29)") (class "Default")
      (node (ref "U1") (pin "29") (pinfunction "IO5_29") (pintype "bidirectional"))
    )
    (net (code "45") (name "unconnected-(U1-IO12-Pad14)") (class "Default")
      (node (ref "U1") (pin "14") (pinfunction "IO12_14") (pintype "bidirectional"))
    )
    (net (code "46") (name "unconnected-(U1-IO13-Pad16)") (class "Default")
      (node (ref "U1") (pin "16") (pinfunction "IO13_16") (pintype "bidirectional"))
    )
    (net (code "47") (name "unconnected-(U1-IO27-Pad12)") (class "Default")
      (node (ref "U1") (pin "12") (pinfunction "IO27_12") (pintype "bidirectional"))
    )
    (net (code "48") (name "unconnected-(U1-NC-Pad32)") (class "Default")
      (node (ref "U1") (pin "32") (pinfunction "NC_32") (pintype "no_connect"))
    )
    (net (code "49") (name "unconnected-(U1-NC_2-Pad17)") (class "Default")
      (node (ref "U1") (pin "17") (pinfunction "NC_2_17") (pintype "no_connect"))
    )
    (net (code "50") (name "unconnected-(U1-NC_3-Pad18)") (class "Default")
      (node (ref "U1") (pin "18") (pinfunction "NC_3_18") (pintype "no_connect"))
    )
    (net (code "51") (name "unconnected-(U1-NC_4-Pad19)") (class "Default")
      (node (ref "U1") (pin "19") (pinfunction "NC_4_19") (pintype "no_connect"))
    )
    (net (code "52") (name "unconnected-(U1-NC_5-Pad20)") (class "Default")
      (node (ref "U1") (pin "20") (pinfunction "NC_5_20") (pintype "no_connect"))
    )
    (net (code "53") (name "unconnected-(U1-NC_6-Pad21)") (class "Default")
      (node (ref "U1") (pin "21") (pinfunction "NC_6_21") (pintype "no_connect"))
    )
    (net (code "54") (name "unconnected-(U1-NC_7-Pad22)") (class "Default")
      (node (ref "U1") (pin "22") (pinfunction "NC_7_22") (pintype "no_connect"))
    )
    (net (code "55") (name "unconnected-(U1-NC_8-Pad27)") (class "Default")
      (node (ref "U1") (pin "27") (pinfunction "NC_8_27") (pintype "no_connect"))
    )
    (net (code "56") (name "unconnected-(U1-NC_9-Pad28)") (class "Default")
      (node (ref "U1") (pin "28") (pinfunction "NC_9_28") (pintype "no_connect"))
    )
    (net (code "57") (name "unconnected-(U1-SENSOR_VN-Pad5)") (class "Default")
      (node (ref "U1") (pin "5") (pinfunction "SENSOR_VN_5") (pintype "input"))
    )
    (net (code "58") (name "unconnected-(U1-SENSOR_VP-Pad4)") (class "Default")
      (node (ref "U1") (pin "4") (pinfunction "SENSOR_VP_4") (pintype "input"))
    )
    (net (code "59") (name "unconnected-(U5-R232-Pad15)") (class "Default")
      (node (ref "U5") (pin "15") (pinfunction "R232_15") (pintype "bidirectional"))
    )
    (net (code "60") (name "unconnected-(U5-~{CTS}-Pad9)") (class "Default")
      (node (ref "U5") (pin "9") (pinfunction "~{CTS}_9") (pintype "bidirectional"))
    )
    (net (code "61") (name "unconnected-(U5-~{DCD}-Pad12)") (class "Default")
      (node (ref "U5") (pin "12") (pinfunction "~{DCD}_12") (pintype "bidirectional"))
    )
    (net (code "62") (name "unconnected-(U5-~{DSR}-Pad10)") (class "Default")
      (node (ref "U5") (pin "10") (pinfunction "~{DSR}_10") (pintype "bidirectional"))
    )
    (net (code "63") (name "unconnected-(U5-~{RI}-Pad11)") (class "Default")
      (node (ref "U5") (pin "11") (pinfunction "~{RI}_11") (pintype "bidirectional"))
    )
  )
)
